# log.net
KiCad netlist of a schematic drawn in Altium Designer
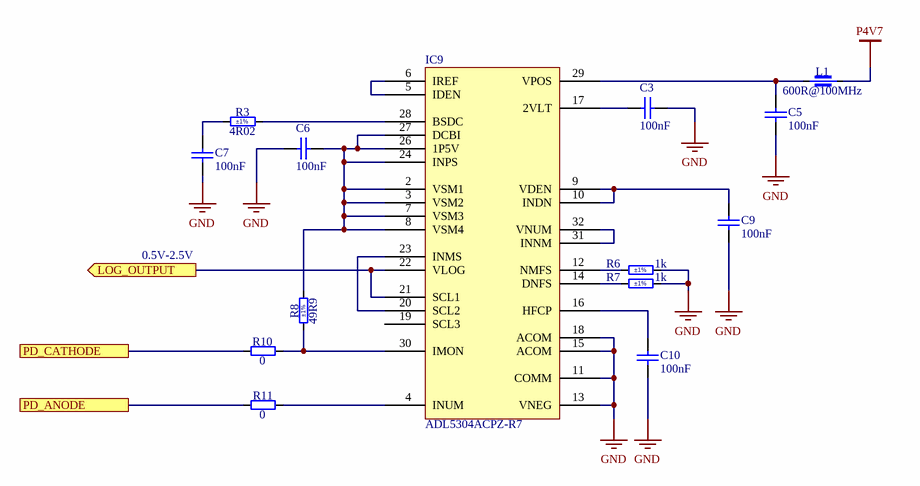
[diagram p0: log.SchDoc]

(export (version "E")
  (design (tool "Eeschema 10.0.6"))
  (components
    (comp (ref "C3")
      (value "100nF")
      (footprint "CAPC1005X55N")
      (description "Non-polarised capacitor")
      (fields
        (field (name "TOLERANCE") "±10%")
        (field (name "VOLTAGE") "16V")
        (field (name "AUTHOR") "CERN DEM JLC")
      )
      (libsource (lib "Capacitors") (part "Capacitor - non polarized"))
    )
    (comp (ref "C5")
      (value "100nF")
      (footprint "CAPC1005X55N")
      (description "Non-polarised capacitor")
      (fields
        (field (name "TOLERANCE") "±10%")
        (field (name "VOLTAGE") "16V")
        (field (name "AUTHOR") "CERN DEM JLC")
      )
      (libsource (lib "Capacitors") (part "Capacitor - non polarized"))
    )
    (comp (ref "C6")
      (value "100nF")
      (footprint "CAPC1005X55N")
      (description "Non-polarised capacitor")
      (fields
        (field (name "TOLERANCE") "±10%")
        (field (name "VOLTAGE") "16V")
        (field (name "AUTHOR") "CERN DEM JLC")
      )
      (libsource (lib "Capacitors") (part "Capacitor - non polarized"))
    )
    (comp (ref "C7")
      (value "100nF")
      (footprint "CAPC1005X55N")
      (description "Non-polarised capacitor")
      (fields
        (field (name "TOLERANCE") "±10%")
        (field (name "VOLTAGE") "16V")
        (field (name "AUTHOR") "CERN DEM JLC")
      )
      (libsource (lib "Capacitors") (part "Capacitor - non polarized"))
    )
    (comp (ref "C9")
      (value "100nF")
      (footprint "CAPC1005X55N")
      (description "Non-polarised capacitor")
      (fields
        (field (name "TOLERANCE") "±10%")
        (field (name "VOLTAGE") "16V")
        (field (name "AUTHOR") "CERN DEM JLC")
      )
      (libsource (lib "Capacitors") (part "Capacitor - non polarized"))
    )
    (comp (ref "C10")
      (value "100nF")
      (footprint "CAPC1005X55N")
      (description "Non-polarised capacitor")
      (fields
        (field (name "TOLERANCE") "±10%")
        (field (name "VOLTAGE") "16V")
        (field (name "AUTHOR") "CERN DEM JLC")
      )
      (libsource (lib "Capacitors") (part "Capacitor - non polarized"))
    )
    (comp (ref "IC9")
      (value "ADL5304ACPZ-R7")
      (footprint "LFCSP32")
      (description "SP Amp LOG Amp Single 5.5V 32-Pin LFCSP EP T/R")
      (fields (field (name "MANUFACTURER") "Analog Devices"))
      (libsource (lib "DiPho") (part "ADL5304ACPZ-R7"))
    )
    (comp (ref "L1")
      (value "600R@100MHz")
      (footprint "INDC1005X55N")
      (fields
        (field (name "PART NUMBER") "IND0402_MURATA_BLM15HD601SN1")
        (field (name "POWER") "300mA")
        (field (name "TOLERANCE") "±25%")
        (field (name "AUTHOR") "CERN DEM JLC")
      )
      (libsource (lib "Inductors & Transformers") (part "Ferrite Bead"))
    )
    (comp (ref "R3")
      (value "4R02")
      (footprint "RESC1005X40N")
      (description "Resistor - 1%")
      (fields
        (field (name "TOLERANCE") "±1%")
        (field (name "PART NUMBER") "R0402_4R02_1%_0.063W_100PPM")
        (field (name "POWER") "0.063W")
        (field (name "AUTHOR") "CERN DEM BC")
      )
      (libsource (lib "Resistors") (part "Resistor - 1%"))
    )
    (comp (ref "R6")
      (value "1k")
      (footprint "RESC1005X40N")
      (description "Resistor - 1%")
      (fields
        (field (name "TOLERANCE") "±1%")
        (field (name "PART NUMBER") "R0402_1K_1%_0.0625W_100PPM")
        (field (name "POWER") "0.0625W")
        (field (name "AUTHOR") "CERN DEM JLC")
      )
      (libsource (lib "Resistors") (part "Resistor - 1%"))
    )
    (comp (ref "R7")
      (value "1k")
      (footprint "RESC1005X40N")
      (description "Resistor - 1%")
      (fields
        (field (name "TOLERANCE") "±1%")
        (field (name "PART NUMBER") "R0402_1K_1%_0.0625W_100PPM")
        (field (name "POWER") "0.0625W")
        (field (name "AUTHOR") "CERN DEM JLC")
      )
      (libsource (lib "Resistors") (part "Resistor - 1%"))
    )
    (comp (ref "R8")
      (value "49R9")
      (footprint "RESC1005X40N")
      (description "Resistor - 1%")
      (fields
        (field (name "TOLERANCE") "±1%")
        (field (name "PART NUMBER") "R0402_49R9_1%_0.0625W_100PPM")
        (field (name "POWER") "0.0625W")
        (field (name "AUTHOR") "CERN DEM JLC")
      )
      (libsource (lib "Resistors") (part "Resistor - 1%"))
    )
    (comp (ref "R10")
      (value "0")
      (footprint "RESC1005X40N")
      (description "Resistor")
      (fields
        (field (name "PART NUMBER") "R0402_0R_JUMPER")
        (field (name "MANUFACTURER") "GENERIC")
        (field (name "AUTHOR") "CERN DEM JLC")
      )
      (libsource (lib "Resistors") (part "Resistor"))
    )
    (comp (ref "R11")
      (value "0")
      (footprint "RESC1005X40N")
      (description "Resistor")
      (fields
        (field (name "PART NUMBER") "R0402_0R_JUMPER")
        (field (name "MANUFACTURER") "GENERIC")
        (field (name "AUTHOR") "CERN DEM JLC")
      )
      (libsource (lib "Resistors") (part "Resistor"))
    )
  )
  (nets
    (net (code "1") (name "/LOG_OUTPUT") (class "Default")
      (node (ref "IC9") (pin "21") (pinfunction "SCL1_21") (pintype "passive"))
      (node (ref "IC9") (pin "22") (pinfunction "VLOG_22") (pintype "passive"))
    )
    (net (code "2") (name "/PD_ANODE") (class "Default")
      (node (ref "R11") (pin "1") (pinfunction "1_1") (pintype "passive"))
    )
    (net (code "3") (name "/PD_CATHODE") (class "Default")
      (node (ref "R10") (pin "1") (pinfunction "1_1") (pintype "passive"))
    )
    (net (code "4") (name "GND") (class "Default")
      (node (ref "C10") (pin "1") (pinfunction "1_1") (pintype "passive"))
      (node (ref "C3") (pin "1") (pinfunction "1_1") (pintype "passive"))
      (node (ref "C5") (pin "1") (pinfunction "1_1") (pintype "passive"))
      (node (ref "C6") (pin "2") (pinfunction "2_2") (pintype "passive"))
      (node (ref "C7") (pin "2") (pinfunction "2_2") (pintype "passive"))
      (node (ref "C9") (pin "1") (pinfunction "1_1") (pintype "passive"))
      (node (ref "IC9") (pin "11") (pinfunction "COMM_11") (pintype "passive"))
      (node (ref "IC9") (pin "13") (pinfunction "VNEG_13") (pintype "passive"))
      (node (ref "IC9") (pin "15") (pinfunction "ACOM_15") (pintype "passive"))
      (node (ref "IC9") (pin "18") (pinfunction "ACOM_18") (pintype "passive"))
      (node (ref "R6") (pin "2") (pinfunction "2_2") (pintype "passive"))
      (node (ref "R7") (pin "2") (pinfunction "2_2") (pintype "passive"))
    )
    (net (code "5") (name "Net-(C7-Pad1)") (class "Default")
      (node (ref "C7") (pin "1") (pinfunction "1_1") (pintype "passive"))
      (node (ref "R3") (pin "1") (pinfunction "1_1") (pintype "passive"))
    )
    (net (code "6") (name "Net-(IC9-1P5V)") (class "Default")
      (node (ref "C6") (pin "1") (pinfunction "1_1") (pintype "passive"))
      (node (ref "IC9") (pin "2") (pinfunction "VSM1_2") (pintype "passive"))
      (node (ref "IC9") (pin "24") (pinfunction "INPS_24") (pintype "passive"))
      (node (ref "IC9") (pin "26") (pinfunction "1P5V_26") (pintype "passive"))
      (node (ref "IC9") (pin "27") (pinfunction "DCBI_27") (pintype "passive"))
      (node (ref "IC9") (pin "3") (pinfunction "VSM2_3") (pintype "passive"))
      (node (ref "IC9") (pin "7") (pinfunction "VSM3_7") (pintype "passive"))
      (node (ref "IC9") (pin "8") (pinfunction "VSM4_8") (pintype "passive"))
      (node (ref "R8") (pin "2") (pinfunction "2_2") (pintype "passive"))
    )
    (net (code "7") (name "Net-(IC9-2VLT)") (class "Default")
      (node (ref "C3") (pin "2") (pinfunction "2_2") (pintype "passive"))
      (node (ref "IC9") (pin "17") (pinfunction "2VLT_17") (pintype "passive"))
    )
    (net (code "8") (name "Net-(IC9-BSDC)") (class "Default")
      (node (ref "IC9") (pin "28") (pinfunction "BSDC_28") (pintype "passive"))
      (node (ref "R3") (pin "2") (pinfunction "2_2") (pintype "passive"))
    )
    (net (code "9") (name "Net-(IC9-DNFS)") (class "Default")
      (node (ref "IC9") (pin "14") (pinfunction "DNFS_14") (pintype "passive"))
      (node (ref "R7") (pin "1") (pinfunction "1_1") (pintype "passive"))
    )
    (net (code "10") (name "Net-(IC9-HFCP)") (class "Default")
      (node (ref "C10") (pin "2") (pinfunction "2_2") (pintype "passive"))
      (node (ref "IC9") (pin "16") (pinfunction "HFCP_16") (pintype "passive"))
    )
    (net (code "11") (name "Net-(IC9-IDEN)") (class "Default")
      (node (ref "IC9") (pin "5") (pinfunction "IDEN_5") (pintype "passive"))
      (node (ref "IC9") (pin "6") (pinfunction "IREF_6") (pintype "passive"))
    )
    (net (code "12") (name "Net-(IC9-IMON)") (class "Default")
      (node (ref "IC9") (pin "30") (pinfunction "IMON_30") (pintype "passive"))
      (node (ref "R10") (pin "2") (pinfunction "2_2") (pintype "passive"))
      (node (ref "R8") (pin "1") (pinfunction "1_1") (pintype "passive"))
    )
    (net (code "13") (name "Net-(IC9-INDN)") (class "Default")
      (node (ref "C9") (pin "2") (pinfunction "2_2") (pintype "passive"))
      (node (ref "IC9") (pin "10") (pinfunction "INDN_10") (pintype "passive"))
      (node (ref "IC9") (pin "9") (pinfunction "VDEN_9") (pintype "passive"))
    )
    (net (code "14") (name "Net-(IC9-INMS)") (class "Default")
      (node (ref "IC9") (pin "20") (pinfunction "SCL2_20") (pintype "passive"))
      (node (ref "IC9") (pin "23") (pinfunction "INMS_23") (pintype "passive"))
    )
    (net (code "15") (name "Net-(IC9-INNM)") (class "Default")
      (node (ref "IC9") (pin "31") (pinfunction "INNM_31") (pintype "passive"))
      (node (ref "IC9") (pin "32") (pinfunction "VNUM_32") (pintype "passive"))
    )
    (net (code "16") (name "Net-(IC9-INUM)") (class "Default")
      (node (ref "IC9") (pin "4") (pinfunction "INUM_4") (pintype "passive"))
      (node (ref "R11") (pin "2") (pinfunction "2_2") (pintype "passive"))
    )
    (net (code "17") (name "Net-(IC9-NMFS)") (class "Default")
      (node (ref "IC9") (pin "12") (pinfunction "NMFS_12") (pintype "passive"))
      (node (ref "R6") (pin "1") (pinfunction "1_1") (pintype "passive"))
    )
    (net (code "18") (name "Net-(IC9-VPOS)") (class "Default")
      (node (ref "C5") (pin "2") (pinfunction "2_2") (pintype "passive"))
      (node (ref "IC9") (pin "29") (pinfunction "VPOS_29") (pintype "passive"))
      (node (ref "L1") (pin "1") (pinfunction "1_1") (pintype "passive"))
    )
    (net (code "19") (name "P4V7") (class "Default")
      (node (ref "L1") (pin "2") (pinfunction "2_2") (pintype "passive"))
    )
    (net (code "20") (name "unconnected-(IC9-SCL3-Pad19)") (class "Default")
      (node (ref "IC9") (pin "19") (pinfunction "SCL3_19") (pintype "passive"))
    )
  )
)
